# SEADLight.net
KiCad netlist of a schematic drawn in EAGLE
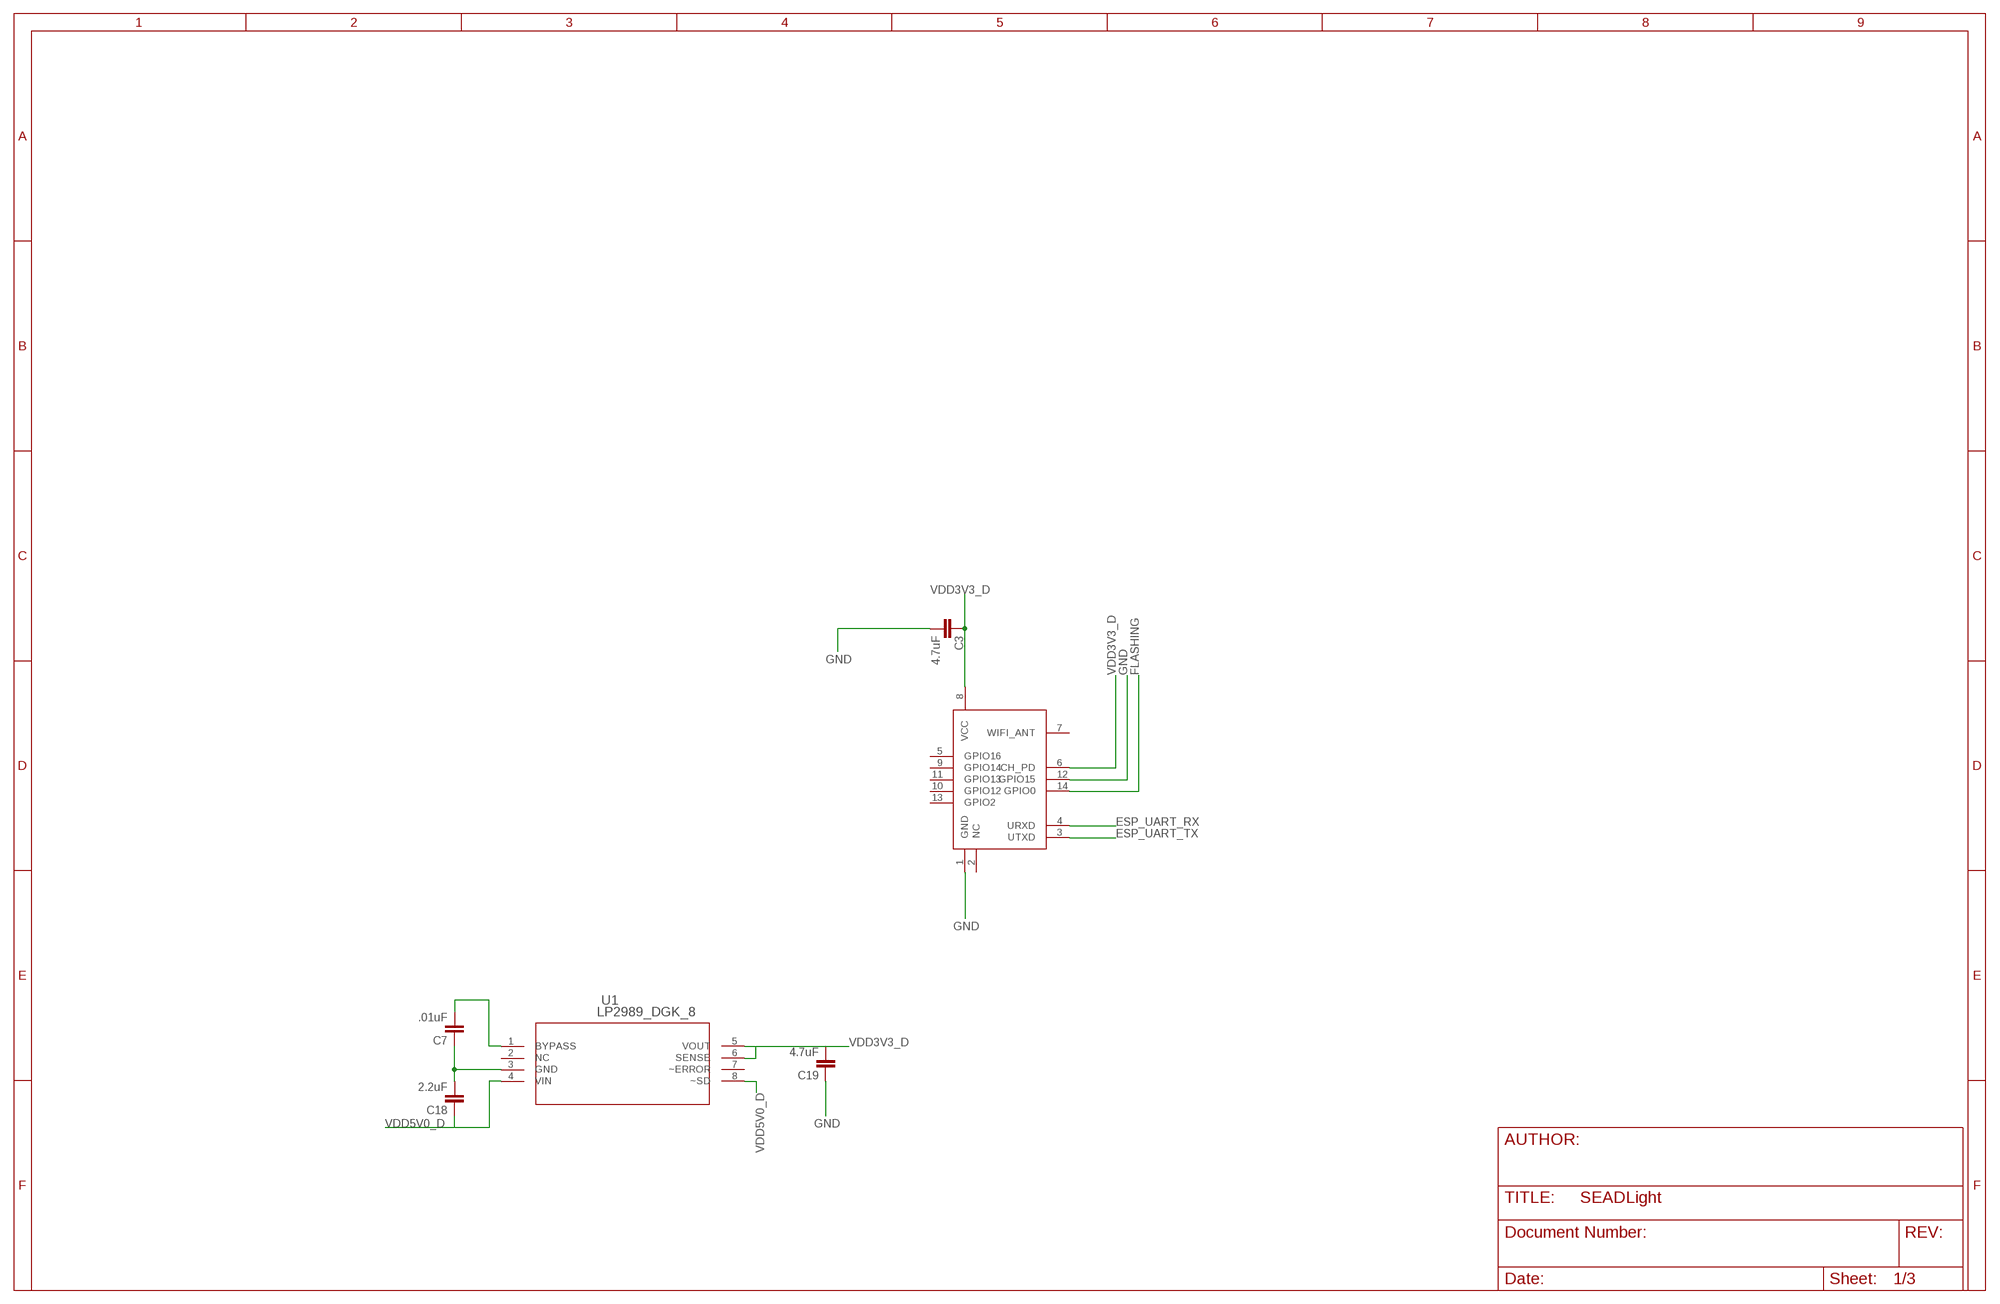
[diagram p0: schematic, sheet 1]
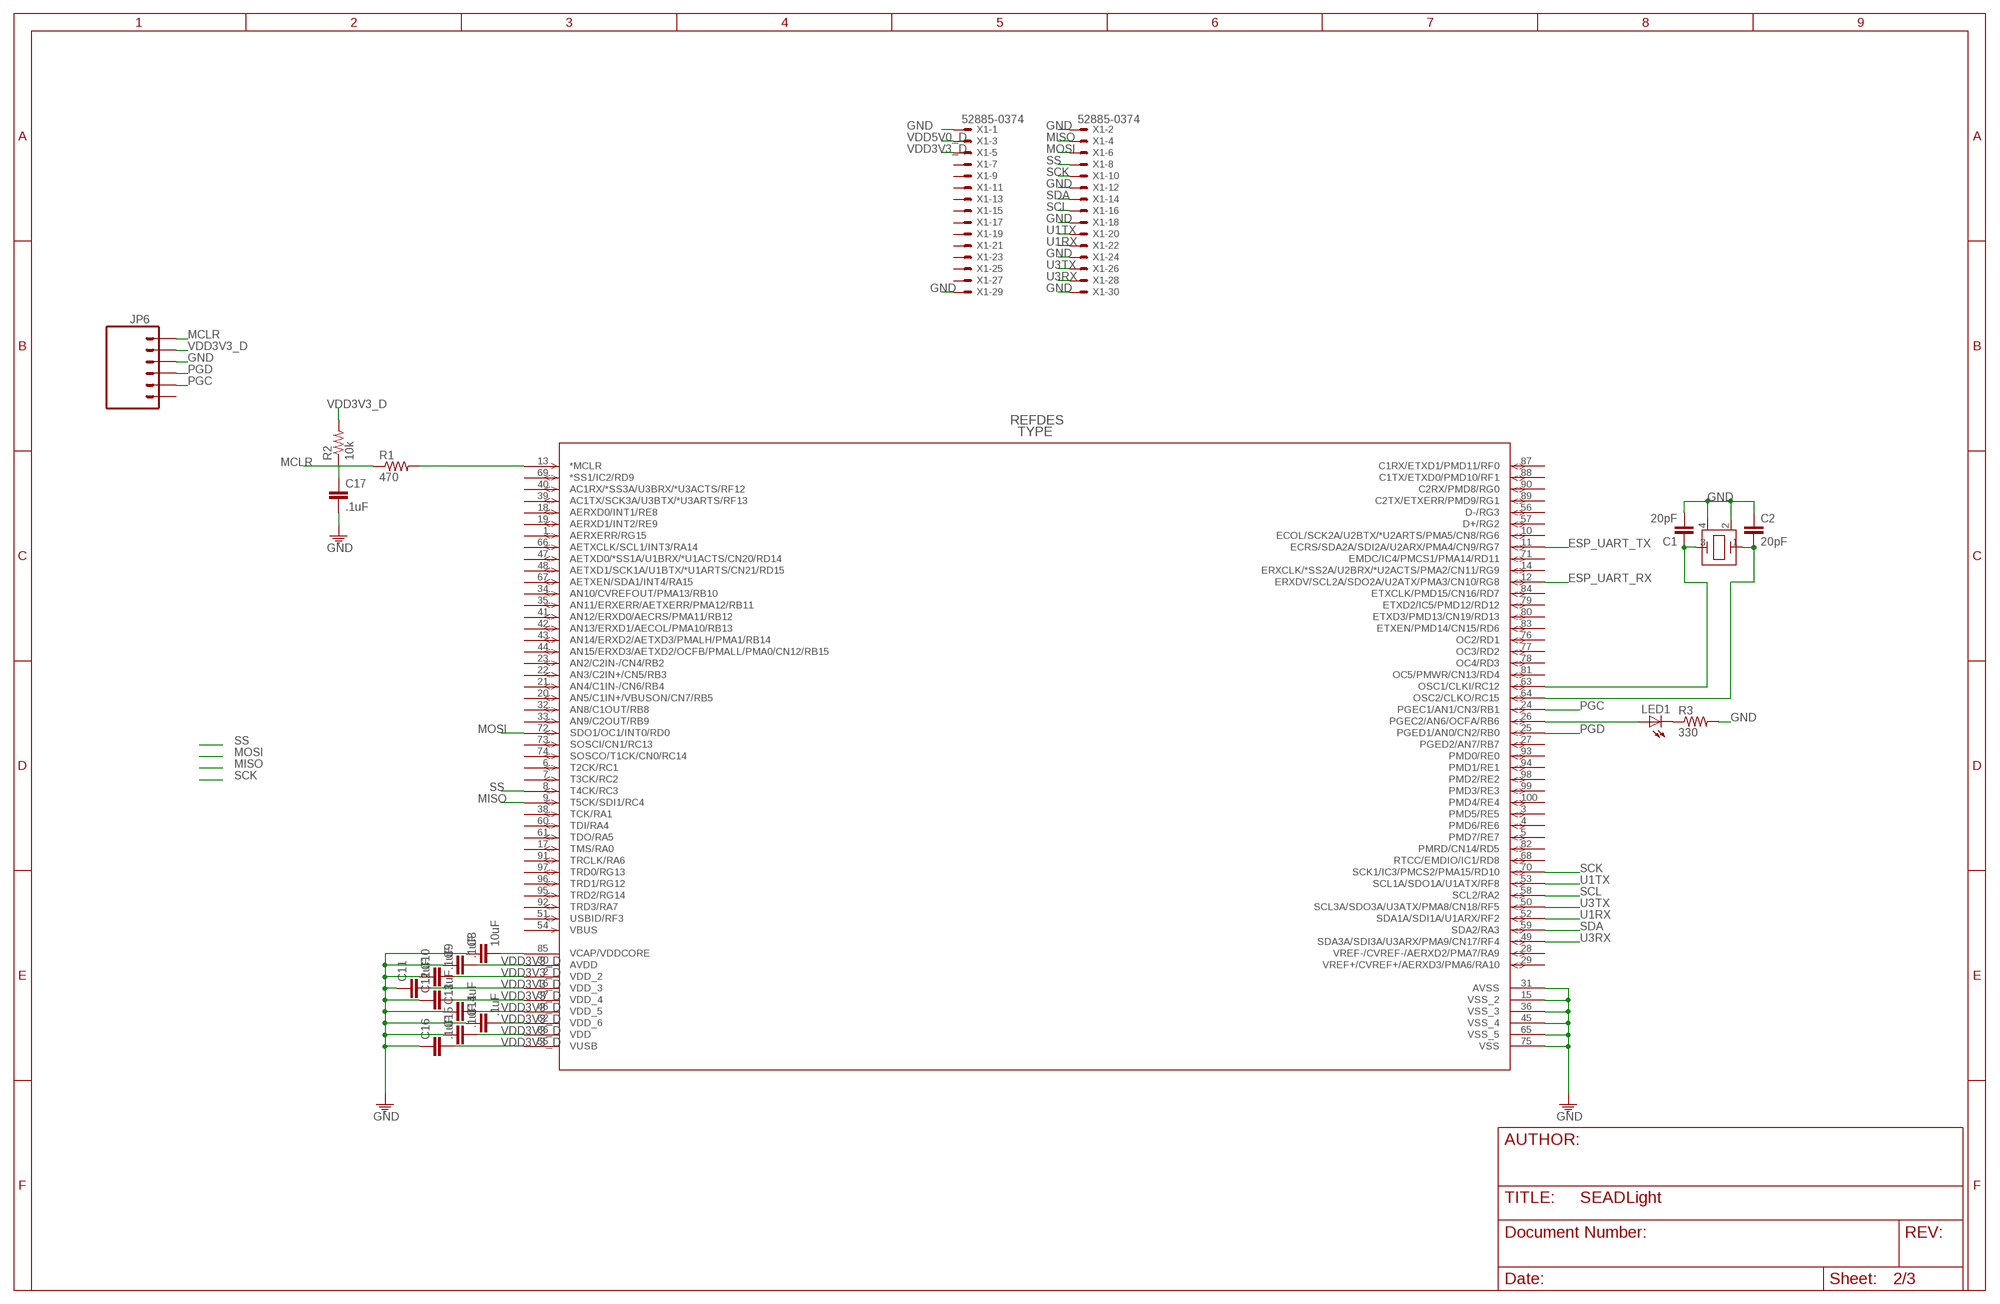
[diagram p1: schematic, sheet 2]
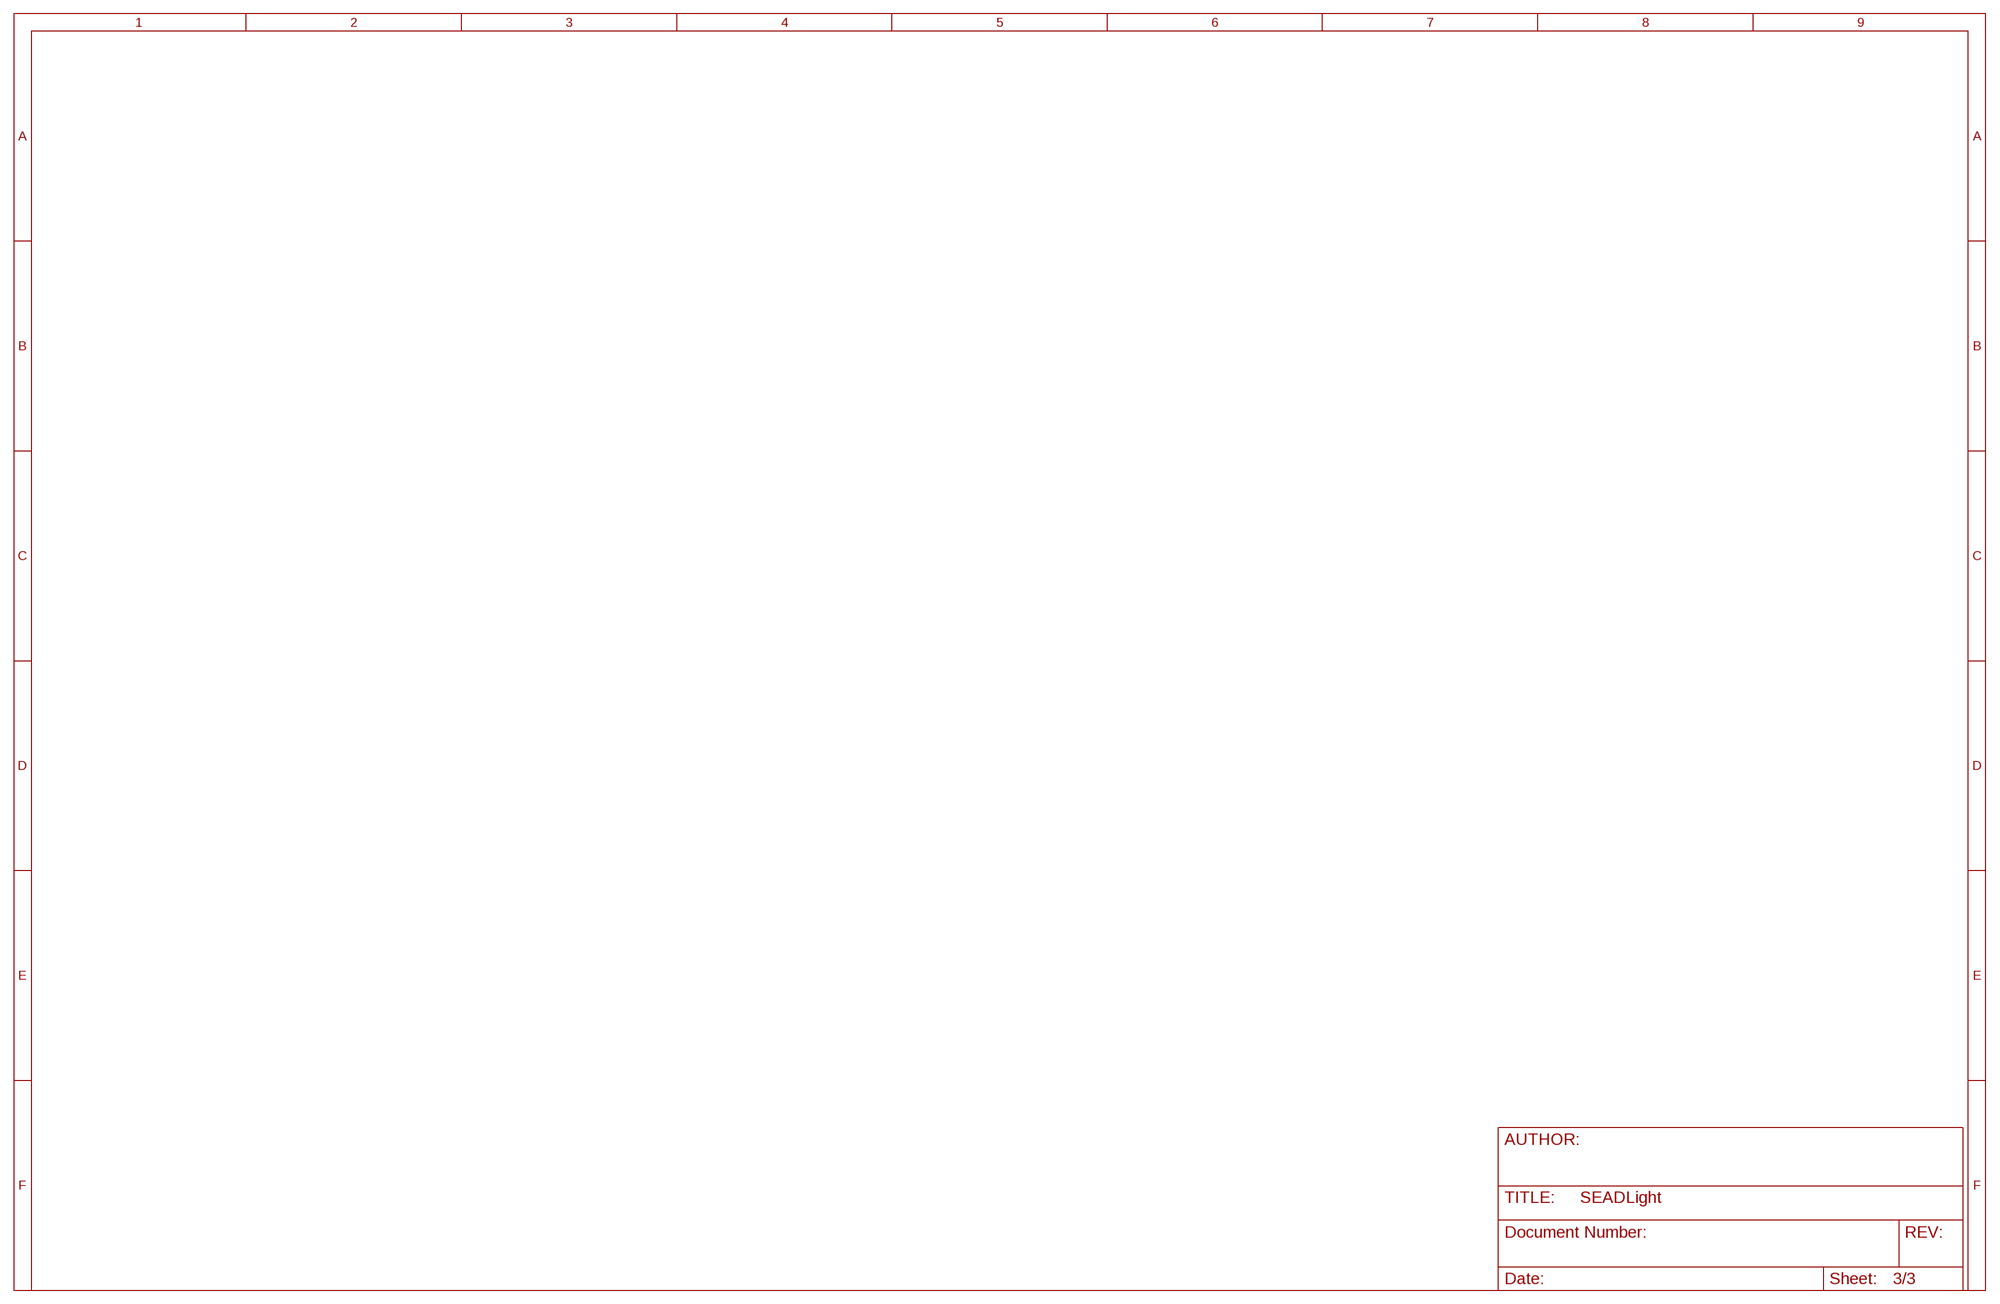
[diagram p2: schematic, sheet 3]

(export (version "E")
  (design (tool "Eeschema 10.0.6"))
  (components
    (comp (ref "C1")
      (value "20pF")
      (footprint "eagle-import:0805")
      (libsource (lib "eagle-import") (part "CAP0805"))
    )
    (comp (ref "C2")
      (value "20pF")
      (footprint "eagle-import:0805")
      (libsource (lib "eagle-import") (part "CAP0805"))
    )
    (comp (ref "C8")
      (value "10uF")
      (footprint "eagle-import:0805")
      (libsource (lib "eagle-import") (part "CAP0805"))
    )
    (comp (ref "C9")
      (value ".1uF")
      (footprint "eagle-import:0805")
      (libsource (lib "eagle-import") (part "CAP0805"))
    )
    (comp (ref "C10")
      (value ".1uF")
      (footprint "eagle-import:0805")
      (libsource (lib "eagle-import") (part "CAP0805"))
    )
    (comp (ref "C11")
      (value ".1uF")
      (footprint "eagle-import:0805")
      (libsource (lib "eagle-import") (part "CAP0805"))
    )
    (comp (ref "C12")
      (value ".1uF")
      (footprint "eagle-import:0805")
      (libsource (lib "eagle-import") (part "CAP0805"))
    )
    (comp (ref "C13")
      (value ".1uF")
      (footprint "eagle-import:0805")
      (libsource (lib "eagle-import") (part "CAP0805"))
    )
    (comp (ref "C14")
      (value ".1uF")
      (footprint "eagle-import:0805")
      (libsource (lib "eagle-import") (part "CAP0805"))
    )
    (comp (ref "C15")
      (value ".1uF")
      (footprint "eagle-import:0805")
      (libsource (lib "eagle-import") (part "CAP0805"))
    )
    (comp (ref "C16")
      (value ".1uF")
      (footprint "eagle-import:0805")
      (libsource (lib "eagle-import") (part "CAP0805"))
    )
    (comp (ref "C17")
      (value ".1uF")
      (footprint "eagle-import:0805")
      (libsource (lib "eagle-import") (part "CAP0805"))
    )
    (comp (ref "JP6")
      (value "M06SIP_LOCK")
      (footprint "eagle-import:1X06-SIP_LOCK")
      (libsource (lib "eagle-import") (part "M06SIP_LOCK"))
    )
    (comp (ref "LED1")
      (value "LED0805")
      (footprint "eagle-import:LED-0805")
      (libsource (lib "eagle-import") (part "LED0805"))
    )
    (comp (ref "R1")
      (value "470")
      (footprint "eagle-import:0805")
      (libsource (lib "eagle-import") (part "RESISTOR0805-RES"))
    )
    (comp (ref "R2")
      (value "10k")
      (footprint "eagle-import:0805")
      (libsource (lib "eagle-import") (part "RESISTOR0805-RES"))
    )
    (comp (ref "R3")
      (value "330")
      (footprint "eagle-import:0805")
      (libsource (lib "eagle-import") (part "RESISTOR0805-RES"))
    )
    (comp (ref "U$1")
      (value "PIC32MX795F512L-")
      (footprint "eagle-import:TQFP100_12X12MC")
      (libsource (lib "eagle-import") (part "PIC32MX795F512L-"))
    )
    (comp (ref "U$2")
      (value "ABM3B-8.000MHZ-10-1-U-T")
      (footprint "eagle-import:ABM3B")
      (libsource (lib "eagle-import") (part "ABM3B-8.000MHZ-10-1-U-T"))
    )
    (comp (ref "X1")
      (value "52885-0374")
      (footprint "eagle-import:52885-0374")
      (fields (field (name "MPN") "52760-0379"))
      (libsource (lib "eagle-import") (part "52885-0374"))
    )
    (comp (ref "C3")
      (value "4.7uF")
      (footprint "eagle-import:0805")
      (libsource (lib "eagle-import") (part "CAP0805"))
    )
    (comp (ref "C7")
      (value ".01uF")
      (footprint "eagle-import:0805")
      (libsource (lib "eagle-import") (part "CAP0805"))
    )
    (comp (ref "C18")
      (value "2.2uF")
      (footprint "eagle-import:0805")
      (libsource (lib "eagle-import") (part "CAP0805"))
    )
    (comp (ref "C19")
      (value "4.7uF")
      (footprint "eagle-import:0805")
      (libsource (lib "eagle-import") (part "CAP0805"))
    )
    (comp (ref "U$3")
      (value "EPS8266")
      (footprint "eagle-import:ESP8266-03")
      (libsource (lib "eagle-import") (part "EPS8266"))
    )
    (comp (ref "U1")
      (value "LP2989_DGK_8")
      (footprint "eagle-import:MUA08A")
      (fields (field (name "PARTNUMBER") "LP2989AIMM-25"))
      (libsource (lib "eagle-import") (part "LP2989_DGK_8"))
    )
  )
  (nets
    (net (code "1") (name "ESP_UART_RX") (class "Default")
      (node (ref "U$1") (pin "12") (pinfunction "ERXDV/SCL2A/SDO2A/U2ATX/PMA3/CN10/RG8_12") (pintype "passive"))
      (node (ref "U$3") (pin "4") (pinfunction "URXD_4") (pintype "bidirectional"))
    )
    (net (code "2") (name "ESP_UART_TX") (class "Default")
      (node (ref "U$1") (pin "11") (pinfunction "ECRS/SDA2A/SDI2A/U2ARX/PMA4/CN9/RG7_11") (pintype "passive"))
      (node (ref "U$3") (pin "3") (pinfunction "UTXD_3") (pintype "bidirectional"))
    )
    (net (code "3") (name "FLASHING") (class "Default")
      (node (ref "U$3") (pin "14") (pinfunction "GPIO0_14") (pintype "bidirectional"))
    )
    (net (code "4") (name "GND") (class "Default")
      (node (ref "C1") (pin "2") (pinfunction "2_2") (pintype "passive"))
      (node (ref "C10") (pin "1") (pinfunction "1_1") (pintype "passive"))
      (node (ref "C11") (pin "1") (pinfunction "1_1") (pintype "passive"))
      (node (ref "C12") (pin "1") (pinfunction "1_1") (pintype "passive"))
      (node (ref "C13") (pin "1") (pinfunction "1_1") (pintype "passive"))
      (node (ref "C14") (pin "1") (pinfunction "1_1") (pintype "passive"))
      (node (ref "C15") (pin "1") (pinfunction "1_1") (pintype "passive"))
      (node (ref "C16") (pin "1") (pinfunction "1_1") (pintype "passive"))
      (node (ref "C17") (pin "2") (pinfunction "2_2") (pintype "passive"))
      (node (ref "C18") (pin "2") (pinfunction "2_2") (pintype "passive"))
      (node (ref "C19") (pin "1") (pinfunction "1_1") (pintype "passive"))
      (node (ref "C2") (pin "1") (pinfunction "1_1") (pintype "passive"))
      (node (ref "C3") (pin "2") (pinfunction "2_2") (pintype "passive"))
      (node (ref "C7") (pin "1") (pinfunction "1_1") (pintype "passive"))
      (node (ref "C8") (pin "1") (pinfunction "1_1") (pintype "passive"))
      (node (ref "C9") (pin "1") (pinfunction "1_1") (pintype "passive"))
      (node (ref "JP6") (pin "3") (pinfunction "3_3") (pintype "passive"))
      (node (ref "R3") (pin "2") (pinfunction "2_2") (pintype "passive"))
      (node (ref "U$1") (pin "15") (pinfunction "VSS_2_15") (pintype "passive"))
      (node (ref "U$1") (pin "31") (pinfunction "AVSS_31") (pintype "passive"))
      (node (ref "U$1") (pin "36") (pinfunction "VSS_3_36") (pintype "passive"))
      (node (ref "U$1") (pin "45") (pinfunction "VSS_4_45") (pintype "passive"))
      (node (ref "U$1") (pin "65") (pinfunction "VSS_5_65") (pintype "passive"))
      (node (ref "U$1") (pin "75") (pinfunction "VSS_75") (pintype "passive"))
      (node (ref "U$2") (pin "2") (pinfunction "GND1_2") (pintype "bidirectional"))
      (node (ref "U$2") (pin "4") (pinfunction "GND2_4") (pintype "bidirectional"))
      (node (ref "U$3") (pin "1") (pinfunction "GND_1") (pintype "bidirectional"))
      (node (ref "U$3") (pin "12") (pinfunction "GPIO15_12") (pintype "bidirectional"))
      (node (ref "U1") (pin "3") (pinfunction "GND_3") (pintype "passive"))
      (node (ref "X1") (pin "1") (pinfunction "S_1") (pintype "passive"))
      (node (ref "X1") (pin "12") (pinfunction "S_12") (pintype "passive"))
      (node (ref "X1") (pin "18") (pinfunction "S_18") (pintype "passive"))
      (node (ref "X1") (pin "2") (pinfunction "S_2") (pintype "passive"))
      (node (ref "X1") (pin "24") (pinfunction "S_24") (pintype "passive"))
      (node (ref "X1") (pin "29") (pinfunction "S_29") (pintype "passive"))
      (node (ref "X1") (pin "30") (pinfunction "S_30") (pintype "passive"))
    )
    (net (code "5") (name "MCLR") (class "Default")
      (node (ref "C17") (pin "1") (pinfunction "1_1") (pintype "passive"))
      (node (ref "JP6") (pin "1") (pinfunction "1_1") (pintype "passive"))
      (node (ref "R1") (pin "1") (pinfunction "1_1") (pintype "passive"))
      (node (ref "R2") (pin "1") (pinfunction "1_1") (pintype "passive"))
    )
    (net (code "6") (name "MISO") (class "Default")
      (node (ref "U$1") (pin "9") (pinfunction "T5CK/SDI1/RC4_9") (pintype "passive"))
      (node (ref "X1") (pin "4") (pinfunction "S_4") (pintype "passive"))
    )
    (net (code "7") (name "MOSI") (class "Default")
      (node (ref "U$1") (pin "72") (pinfunction "SDO1/OC1/INT0/RD0_72") (pintype "passive"))
      (node (ref "X1") (pin "6") (pinfunction "S_6") (pintype "passive"))
    )
    (net (code "8") (name "Net-(LED1-A)") (class "Default")
      (node (ref "LED1") (pin "1") (pinfunction "A_1") (pintype "passive"))
      (node (ref "U$1") (pin "26") (pinfunction "PGEC2/AN6/OCFA/RB6_26") (pintype "passive"))
    )
    (net (code "9") (name "Net-(LED1-C)") (class "Default")
      (node (ref "LED1") (pin "2") (pinfunction "C_2") (pintype "passive"))
      (node (ref "R3") (pin "1") (pinfunction "1_1") (pintype "passive"))
    )
    (net (code "10") (name "Net-(U$1-*MCLR)") (class "Default")
      (node (ref "R1") (pin "2") (pinfunction "2_2") (pintype "passive"))
      (node (ref "U$1") (pin "13") (pinfunction "*MCLR_13") (pintype "passive"))
    )
    (net (code "11") (name "Net-(U$1-OSC1{slash}CLKI{slash}RC12)") (class "Default")
      (node (ref "C1") (pin "1") (pinfunction "1_1") (pintype "passive"))
      (node (ref "U$1") (pin "63") (pinfunction "OSC1/CLKI/RC12_63") (pintype "passive"))
      (node (ref "U$2") (pin "3") (pinfunction "OSC2_3") (pintype "bidirectional"))
    )
    (net (code "12") (name "Net-(U$1-OSC2{slash}CLKO{slash}RC15)") (class "Default")
      (node (ref "C2") (pin "2") (pinfunction "2_2") (pintype "passive"))
      (node (ref "U$1") (pin "64") (pinfunction "OSC2/CLKO/RC15_64") (pintype "passive"))
      (node (ref "U$2") (pin "1") (pinfunction "OSC1_1") (pintype "bidirectional"))
    )
    (net (code "13") (name "Net-(U$1-VCAP{slash}VDDCORE)") (class "Default")
      (node (ref "C8") (pin "2") (pinfunction "2_2") (pintype "passive"))
      (node (ref "U$1") (pin "85") (pinfunction "VCAP/VDDCORE_85") (pintype "passive"))
    )
    (net (code "14") (name "Net-(U1-BYPASS)") (class "Default")
      (node (ref "C7") (pin "2") (pinfunction "2_2") (pintype "passive"))
      (node (ref "U1") (pin "1") (pinfunction "BYPASS_1") (pintype "passive"))
    )
    (net (code "15") (name "PGC") (class "Default")
      (node (ref "JP6") (pin "5") (pinfunction "5_5") (pintype "passive"))
      (node (ref "U$1") (pin "24") (pinfunction "PGEC1/AN1/CN3/RB1_24") (pintype "passive"))
    )
    (net (code "16") (name "PGD") (class "Default")
      (node (ref "JP6") (pin "4") (pinfunction "4_4") (pintype "passive"))
      (node (ref "U$1") (pin "25") (pinfunction "PGED1/AN0/CN2/RB0_25") (pintype "passive"))
    )
    (net (code "17") (name "SCK") (class "Default")
      (node (ref "U$1") (pin "70") (pinfunction "SCK1/IC3/PMCS2/PMA15/RD10_70") (pintype "passive"))
      (node (ref "X1") (pin "10") (pinfunction "S_10") (pintype "passive"))
    )
    (net (code "18") (name "SCL") (class "Default")
      (node (ref "U$1") (pin "58") (pinfunction "SCL2/RA2_58") (pintype "passive"))
      (node (ref "X1") (pin "16") (pinfunction "S_16") (pintype "passive"))
    )
    (net (code "19") (name "SDA") (class "Default")
      (node (ref "U$1") (pin "59") (pinfunction "SDA2/RA3_59") (pintype "passive"))
      (node (ref "X1") (pin "14") (pinfunction "S_14") (pintype "passive"))
    )
    (net (code "20") (name "SS") (class "Default")
      (node (ref "U$1") (pin "8") (pinfunction "T4CK/RC3_8") (pintype "passive"))
      (node (ref "X1") (pin "8") (pinfunction "S_8") (pintype "passive"))
    )
    (net (code "21") (name "U1RX") (class "Default")
      (node (ref "U$1") (pin "52") (pinfunction "SDA1A/SDI1A/U1ARX/RF2_52") (pintype "passive"))
      (node (ref "X1") (pin "22") (pinfunction "S_22") (pintype "passive"))
    )
    (net (code "22") (name "U1TX") (class "Default")
      (node (ref "U$1") (pin "53") (pinfunction "SCL1A/SDO1A/U1ATX/RF8_53") (pintype "passive"))
      (node (ref "X1") (pin "20") (pinfunction "S_20") (pintype "passive"))
    )
    (net (code "23") (name "U3RX") (class "Default")
      (node (ref "U$1") (pin "49") (pinfunction "SDA3A/SDI3A/U3ARX/PMA9/CN17/RF4_49") (pintype "passive"))
      (node (ref "X1") (pin "28") (pinfunction "S_28") (pintype "passive"))
    )
    (net (code "24") (name "U3TX") (class "Default")
      (node (ref "U$1") (pin "50") (pinfunction "SCL3A/SDO3A/U3ATX/PMA8/CN18/RF5_50") (pintype "passive"))
      (node (ref "X1") (pin "26") (pinfunction "S_26") (pintype "passive"))
    )
    (net (code "25") (name "VDD3V3_D") (class "Default")
      (node (ref "C10") (pin "2") (pinfunction "2_2") (pintype "passive"))
      (node (ref "C11") (pin "2") (pinfunction "2_2") (pintype "passive"))
      (node (ref "C12") (pin "2") (pinfunction "2_2") (pintype "passive"))
      (node (ref "C13") (pin "2") (pinfunction "2_2") (pintype "passive"))
      (node (ref "C14") (pin "2") (pinfunction "2_2") (pintype "passive"))
      (node (ref "C15") (pin "2") (pinfunction "2_2") (pintype "passive"))
      (node (ref "C16") (pin "2") (pinfunction "2_2") (pintype "passive"))
      (node (ref "C19") (pin "2") (pinfunction "2_2") (pintype "passive"))
      (node (ref "C3") (pin "1") (pinfunction "1_1") (pintype "passive"))
      (node (ref "C9") (pin "2") (pinfunction "2_2") (pintype "passive"))
      (node (ref "JP6") (pin "2") (pinfunction "2_2") (pintype "passive"))
      (node (ref "R2") (pin "2") (pinfunction "2_2") (pintype "passive"))
      (node (ref "U$1") (pin "16") (pinfunction "VDD_3_16") (pintype "passive"))
      (node (ref "U$1") (pin "2") (pinfunction "VDD_2_2") (pintype "passive"))
      (node (ref "U$1") (pin "30") (pinfunction "AVDD_30") (pintype "passive"))
      (node (ref "U$1") (pin "37") (pinfunction "VDD_4_37") (pintype "passive"))
      (node (ref "U$1") (pin "46") (pinfunction "VDD_5_46") (pintype "passive"))
      (node (ref "U$1") (pin "55") (pinfunction "VUSB_55") (pintype "passive"))
      (node (ref "U$1") (pin "62") (pinfunction "VDD_6_62") (pintype "passive"))
      (node (ref "U$1") (pin "86") (pinfunction "VDD_86") (pintype "passive"))
      (node (ref "U$3") (pin "6") (pinfunction "CH_PD_6") (pintype "bidirectional"))
      (node (ref "U$3") (pin "8") (pinfunction "VCC_8") (pintype "bidirectional"))
      (node (ref "U1") (pin "5") (pinfunction "VOUT_5") (pintype "output"))
      (node (ref "U1") (pin "6") (pinfunction "SENSE_6") (pintype "passive"))
      (node (ref "X1") (pin "5") (pinfunction "S_5") (pintype "passive"))
    )
    (net (code "26") (name "VDD5V0_D") (class "Default")
      (node (ref "C18") (pin "1") (pinfunction "1_1") (pintype "passive"))
      (node (ref "U1") (pin "4") (pinfunction "VIN_4") (pintype "input"))
      (node (ref "U1") (pin "8") (pinfunction "~{SD}_8") (pintype "passive"))
      (node (ref "X1") (pin "3") (pinfunction "S_3") (pintype "passive"))
    )
    (net (code "27") (name "unconnected-(JP6-Pad6)") (class "Default")
      (node (ref "JP6") (pin "6") (pinfunction "6_6") (pintype "passive"))
    )
    (net (code "28") (name "unconnected-(U$1-*SS1{slash}IC2{slash}RD9-Pad69)") (class "Default")
      (node (ref "U$1") (pin "69") (pinfunction "*SS1/IC2/RD9_69") (pintype "passive"))
    )
    (net (code "29") (name "unconnected-(U$1-AC1RX{slash}*SS3A{slash}U3BRX{slash}*U3ACTS{slash}RF12-Pad40)") (class "Default")
      (node (ref "U$1") (pin "40") (pinfunction "AC1RX/*SS3A/U3BRX/*U3ACTS/RF12_40") (pintype "passive"))
    )
    (net (code "30") (name "unconnected-(U$1-AC1TX{slash}SCK3A{slash}U3BTX{slash}*U3ARTS{slash}RF13-Pad39)") (class "Default")
      (node (ref "U$1") (pin "39") (pinfunction "AC1TX/SCK3A/U3BTX/*U3ARTS/RF13_39") (pintype "passive"))
    )
    (net (code "31") (name "unconnected-(U$1-AERXD0{slash}INT1{slash}RE8-Pad18)") (class "Default")
      (node (ref "U$1") (pin "18") (pinfunction "AERXD0/INT1/RE8_18") (pintype "passive"))
    )
    (net (code "32") (name "unconnected-(U$1-AERXD1{slash}INT2{slash}RE9-Pad19)") (class "Default")
      (node (ref "U$1") (pin "19") (pinfunction "AERXD1/INT2/RE9_19") (pintype "passive"))
    )
    (net (code "33") (name "unconnected-(U$1-AERXERR{slash}RG15-Pad1)") (class "Default")
      (node (ref "U$1") (pin "1") (pinfunction "AERXERR/RG15_1") (pintype "passive"))
    )
    (net (code "34") (name "unconnected-(U$1-AETXCLK{slash}SCL1{slash}INT3{slash}RA14-Pad66)") (class "Default")
      (node (ref "U$1") (pin "66") (pinfunction "AETXCLK/SCL1/INT3/RA14_66") (pintype "passive"))
    )
    (net (code "35") (name "unconnected-(U$1-AETXD0{slash}*SS1A{slash}U1BRX{slash}*U1ACTS{slash}CN20{slash}RD14-Pad47)") (class "Default")
      (node (ref "U$1") (pin "47") (pinfunction "AETXD0/*SS1A/U1BRX/*U1ACTS/CN20/RD14_47") (pintype "passive"))
    )
    (net (code "36") (name "unconnected-(U$1-AETXD1{slash}SCK1A{slash}U1BTX{slash}*U1ARTS{slash}CN21{slash}RD15-Pad48)") (class "Default")
      (node (ref "U$1") (pin "48") (pinfunction "AETXD1/SCK1A/U1BTX/*U1ARTS/CN21/RD15_48") (pintype "passive"))
    )
    (net (code "37") (name "unconnected-(U$1-AETXEN{slash}SDA1{slash}INT4{slash}RA15-Pad67)") (class "Default")
      (node (ref "U$1") (pin "67") (pinfunction "AETXEN/SDA1/INT4/RA15_67") (pintype "passive"))
    )
    (net (code "38") (name "unconnected-(U$1-AN2{slash}C2IN-{slash}CN4{slash}RB2-Pad23)") (class "Default")
      (node (ref "U$1") (pin "23") (pinfunction "AN2/C2IN-/CN4/RB2_23") (pintype "passive"))
    )
    (net (code "39") (name "unconnected-(U$1-AN3{slash}C2IN+{slash}CN5{slash}RB3-Pad22)") (class "Default")
      (node (ref "U$1") (pin "22") (pinfunction "AN3/C2IN+/CN5/RB3_22") (pintype "passive"))
    )
    (net (code "40") (name "unconnected-(U$1-AN4{slash}C1IN-{slash}CN6{slash}RB4-Pad21)") (class "Default")
      (node (ref "U$1") (pin "21") (pinfunction "AN4/C1IN-/CN6/RB4_21") (pintype "passive"))
    )
    (net (code "41") (name "unconnected-(U$1-AN5{slash}C1IN+{slash}VBUSON{slash}CN7{slash}RB5-Pad20)") (class "Default")
      (node (ref "U$1") (pin "20") (pinfunction "AN5/C1IN+/VBUSON/CN7/RB5_20") (pintype "passive"))
    )
    (net (code "42") (name "unconnected-(U$1-AN8{slash}C1OUT{slash}RB8-Pad32)") (class "Default")
      (node (ref "U$1") (pin "32") (pinfunction "AN8/C1OUT/RB8_32") (pintype "passive"))
    )
    (net (code "43") (name "unconnected-(U$1-AN9{slash}C2OUT{slash}RB9-Pad33)") (class "Default")
      (node (ref "U$1") (pin "33") (pinfunction "AN9/C2OUT/RB9_33") (pintype "passive"))
    )
    (net (code "44") (name "unconnected-(U$1-AN10{slash}CVREFOUT{slash}PMA13{slash}RB10-Pad34)") (class "Default")
      (node (ref "U$1") (pin "34") (pinfunction "AN10/CVREFOUT/PMA13/RB10_34") (pintype "passive"))
    )
    (net (code "45") (name "unconnected-(U$1-AN11{slash}ERXERR{slash}AETXERR{slash}PMA12{slash}RB11-Pad35)") (class "Default")
      (node (ref "U$1") (pin "35") (pinfunction "AN11/ERXERR/AETXERR/PMA12/RB11_35") (pintype "passive"))
    )
    (net (code "46") (name "unconnected-(U$1-AN12{slash}ERXD0{slash}AECRS{slash}PMA11{slash}RB12-Pad41)") (class "Default")
      (node (ref "U$1") (pin "41") (pinfunction "AN12/ERXD0/AECRS/PMA11/RB12_41") (pintype "passive"))
    )
    (net (code "47") (name "unconnected-(U$1-AN13{slash}ERXD1{slash}AECOL{slash}PMA10{slash}RB13-Pad42)") (class "Default")
      (node (ref "U$1") (pin "42") (pinfunction "AN13/ERXD1/AECOL/PMA10/RB13_42") (pintype "passive"))
    )
    (net (code "48") (name "unconnected-(U$1-AN14{slash}ERXD2{slash}AETXD3{slash}PMALH{slash}PMA1{slash}RB14-Pad43)") (class "Default")
      (node (ref "U$1") (pin "43") (pinfunction "AN14/ERXD2/AETXD3/PMALH/PMA1/RB14_43") (pintype "passive"))
    )
    (net (code "49") (name "unconnected-(U$1-AN15{slash}ERXD3{slash}AETXD2{slash}OCFB{slash}PMALL{slash}PMA0{slash}CN12{slash}RB15-Pad44)") (class "Default")
      (node (ref "U$1") (pin "44") (pinfunction "AN15/ERXD3/AETXD2/OCFB/PMALL/PMA0/CN12/RB15_44") (pintype "passive"))
    )
    (net (code "50") (name "unconnected-(U$1-C1RX{slash}ETXD1{slash}PMD11{slash}RF0-Pad87)") (class "Default")
      (node (ref "U$1") (pin "87") (pinfunction "C1RX/ETXD1/PMD11/RF0_87") (pintype "passive"))
    )
    (net (code "51") (name "unconnected-(U$1-C1TX{slash}ETXD0{slash}PMD10{slash}RF1-Pad88)") (class "Default")
      (node (ref "U$1") (pin "88") (pinfunction "C1TX/ETXD0/PMD10/RF1_88") (pintype "passive"))
    )
    (net (code "52") (name "unconnected-(U$1-C2RX{slash}PMD8{slash}RG0-Pad90)") (class "Default")
      (node (ref "U$1") (pin "90") (pinfunction "C2RX/PMD8/RG0_90") (pintype "passive"))
    )
    (net (code "53") (name "unconnected-(U$1-C2TX{slash}ETXERR{slash}PMD9{slash}RG1-Pad89)") (class "Default")
      (node (ref "U$1") (pin "89") (pinfunction "C2TX/ETXERR/PMD9/RG1_89") (pintype "passive"))
    )
    (net (code "54") (name "unconnected-(U$1-D+{slash}RG2-Pad57)") (class "Default")
      (node (ref "U$1") (pin "57") (pinfunction "D+/RG2_57") (pintype "passive"))
    )
    (net (code "55") (name "unconnected-(U$1-D-{slash}RG3-Pad56)") (class "Default")
      (node (ref "U$1") (pin "56") (pinfunction "D-/RG3_56") (pintype "passive"))
    )
    (net (code "56") (name "unconnected-(U$1-ECOL{slash}SCK2A{slash}U2BTX{slash}*U2ARTS{slash}PMA5{slash}CN8{slash}RG6-Pad10)") (class "Default")
      (node (ref "U$1") (pin "10") (pinfunction "ECOL/SCK2A/U2BTX/*U2ARTS/PMA5/CN8/RG6_10") (pintype "passive"))
    )
    (net (code "57") (name "unconnected-(U$1-EMDC{slash}IC4{slash}PMCS1{slash}PMA14{slash}RD11-Pad71)") (class "Default")
      (node (ref "U$1") (pin "71") (pinfunction "EMDC/IC4/PMCS1/PMA14/RD11_71") (pintype "passive"))
    )
    (net (code "58") (name "unconnected-(U$1-ERXCLK{slash}*SS2A{slash}U2BRX{slash}*U2ACTS{slash}PMA2{slash}CN11{slash}RG9-Pad14)") (class "Default")
      (node (ref "U$1") (pin "14") (pinfunction "ERXCLK/*SS2A/U2BRX/*U2ACTS/PMA2/CN11/RG9_14") (pintype "passive"))
    )
    (net (code "59") (name "unconnected-(U$1-ETXCLK{slash}PMD15{slash}CN16{slash}RD7-Pad84)") (class "Default")
      (node (ref "U$1") (pin "84") (pinfunction "ETXCLK/PMD15/CN16/RD7_84") (pintype "passive"))
    )
    (net (code "60") (name "unconnected-(U$1-ETXD2{slash}IC5{slash}PMD12{slash}RD12-Pad79)") (class "Default")
      (node (ref "U$1") (pin "79") (pinfunction "ETXD2/IC5/PMD12/RD12_79") (pintype "passive"))
    )
    (net (code "61") (name "unconnected-(U$1-ETXD3{slash}PMD13{slash}CN19{slash}RD13-Pad80)") (class "Default")
      (node (ref "U$1") (pin "80") (pinfunction "ETXD3/PMD13/CN19/RD13_80") (pintype "passive"))
    )
    (net (code "62") (name "unconnected-(U$1-ETXEN{slash}PMD14{slash}CN15{slash}RD6-Pad83)") (class "Default")
      (node (ref "U$1") (pin "83") (pinfunction "ETXEN/PMD14/CN15/RD6_83") (pintype "passive"))
    )
    (net (code "63") (name "unconnected-(U$1-OC2{slash}RD1-Pad76)") (class "Default")
      (node (ref "U$1") (pin "76") (pinfunction "OC2/RD1_76") (pintype "passive"))
    )
    (net (code "64") (name "unconnected-(U$1-OC3{slash}RD2-Pad77)") (class "Default")
      (node (ref "U$1") (pin "77") (pinfunction "OC3/RD2_77") (pintype "passive"))
    )
    (net (code "65") (name "unconnected-(U$1-OC4{slash}RD3-Pad78)") (class "Default")
      (node (ref "U$1") (pin "78") (pinfunction "OC4/RD3_78") (pintype "passive"))
    )
    (net (code "66") (name "unconnected-(U$1-OC5{slash}PMWR{slash}CN13{slash}RD4-Pad81)") (class "Default")
      (node (ref "U$1") (pin "81") (pinfunction "OC5/PMWR/CN13/RD4_81") (pintype "passive"))
    )
    (net (code "67") (name "unconnected-(U$1-PGED2{slash}AN7{slash}RB7-Pad27)") (class "Default")
      (node (ref "U$1") (pin "27") (pinfunction "PGED2/AN7/RB7_27") (pintype "passive"))
    )
    (net (code "68") (name "unconnected-(U$1-PMD0{slash}RE0-Pad93)") (class "Default")
      (node (ref "U$1") (pin "93") (pinfunction "PMD0/RE0_93") (pintype "passive"))
    )
    (net (code "69") (name "unconnected-(U$1-PMD1{slash}RE1-Pad94)") (class "Default")
      (node (ref "U$1") (pin "94") (pinfunction "PMD1/RE1_94") (pintype "passive"))
    )
    (net (code "70") (name "unconnected-(U$1-PMD2{slash}RE2-Pad98)") (class "Default")
      (node (ref "U$1") (pin "98") (pinfunction "PMD2/RE2_98") (pintype "passive"))
    )
    (net (code "71") (name "unconnected-(U$1-PMD3{slash}RE3-Pad99)") (class "Default")
      (node (ref "U$1") (pin "99") (pinfunction "PMD3/RE3_99") (pintype "passive"))
    )
    (net (code "72") (name "unconnected-(U$1-PMD4{slash}RE4-Pad100)") (class "Default")
      (node (ref "U$1") (pin "100") (pinfunction "PMD4/RE4_100") (pintype "passive"))
    )
    (net (code "73") (name "unconnected-(U$1-PMD5{slash}RE5-Pad3)") (class "Default")
      (node (ref "U$1") (pin "3") (pinfunction "PMD5/RE5_3") (pintype "passive"))
    )
    (net (code "74") (name "unconnected-(U$1-PMD6{slash}RE6-Pad4)") (class "Default")
      (node (ref "U$1") (pin "4") (pinfunction "PMD6/RE6_4") (pintype "passive"))
    )
    (net (code "75") (name "unconnected-(U$1-PMD7{slash}RE7-Pad5)") (class "Default")
      (node (ref "U$1") (pin "5") (pinfunction "PMD7/RE7_5") (pintype "passive"))
    )
    (net (code "76") (name "unconnected-(U$1-PMRD{slash}CN14{slash}RD5-Pad82)") (class "Default")
      (node (ref "U$1") (pin "82") (pinfunction "PMRD/CN14/RD5_82") (pintype "passive"))
    )
    (net (code "77") (name "unconnected-(U$1-RTCC{slash}EMDIO{slash}IC1{slash}RD8-Pad68)") (class "Default")
      (node (ref "U$1") (pin "68") (pinfunction "RTCC/EMDIO/IC1/RD8_68") (pintype "passive"))
    )
    (net (code "78") (name "unconnected-(U$1-SOSCI{slash}CN1{slash}RC13-Pad73)") (class "Default")
      (node (ref "U$1") (pin "73") (pinfunction "SOSCI/CN1/RC13_73") (pintype "passive"))
    )
    (net (code "79") (name "unconnected-(U$1-SOSCO{slash}T1CK{slash}CN0{slash}RC14-Pad74)") (class "Default")
      (node (ref "U$1") (pin "74") (pinfunction "SOSCO/T1CK/CN0/RC14_74") (pintype "passive"))
    )
    (net (code "80") (name "unconnected-(U$1-T2CK{slash}RC1-Pad6)") (class "Default")
      (node (ref "U$1") (pin "6") (pinfunction "T2CK/RC1_6") (pintype "passive"))
    )
    (net (code "81") (name "unconnected-(U$1-T3CK{slash}RC2-Pad7)") (class "Default")
      (node (ref "U$1") (pin "7") (pinfunction "T3CK/RC2_7") (pintype "passive"))
    )
    (net (code "82") (name "unconnected-(U$1-TCK{slash}RA1-Pad38)") (class "Default")
      (node (ref "U$1") (pin "38") (pinfunction "TCK/RA1_38") (pintype "passive"))
    )
    (net (code "83") (name "unconnected-(U$1-TDI{slash}RA4-Pad60)") (class "Default")
      (node (ref "U$1") (pin "60") (pinfunction "TDI/RA4_60") (pintype "passive"))
    )
    (net (code "84") (name "unconnected-(U$1-TDO{slash}RA5-Pad61)") (class "Default")
      (node (ref "U$1") (pin "61") (pinfunction "TDO/RA5_61") (pintype "passive"))
    )
    (net (code "85") (name "unconnected-(U$1-TMS{slash}RA0-Pad17)") (class "Default")
      (node (ref "U$1") (pin "17") (pinfunction "TMS/RA0_17") (pintype "passive"))
    )
    (net (code "86") (name "unconnected-(U$1-TRCLK{slash}RA6-Pad91)") (class "Default")
      (node (ref "U$1") (pin "91") (pinfunction "TRCLK/RA6_91") (pintype "passive"))
    )
    (net (code "87") (name "unconnected-(U$1-TRD0{slash}RG13-Pad97)") (class "Default")
      (node (ref "U$1") (pin "97") (pinfunction "TRD0/RG13_97") (pintype "passive"))
    )
    (net (code "88") (name "unconnected-(U$1-TRD1{slash}RG12-Pad96)") (class "Default")
      (node (ref "U$1") (pin "96") (pinfunction "TRD1/RG12_96") (pintype "passive"))
    )
    (net (code "89") (name "unconnected-(U$1-TRD2{slash}RG14-Pad95)") (class "Default")
      (node (ref "U$1") (pin "95") (pinfunction "TRD2/RG14_95") (pintype "passive"))
    )
    (net (code "90") (name "unconnected-(U$1-TRD3{slash}RA7-Pad92)") (class "Default")
      (node (ref "U$1") (pin "92") (pinfunction "TRD3/RA7_92") (pintype "passive"))
    )
    (net (code "91") (name "unconnected-(U$1-USBID{slash}RF3-Pad51)") (class "Default")
      (node (ref "U$1") (pin "51") (pinfunction "USBID/RF3_51") (pintype "passive"))
    )
    (net (code "92") (name "unconnected-(U$1-VBUS-Pad54)") (class "Default")
      (node (ref "U$1") (pin "54") (pinfunction "VBUS_54") (pintype "passive"))
    )
    (net (code "93") (name "unconnected-(U$1-VREF+{slash}CVREF+{slash}AERXD3{slash}PMA6{slash}RA10-Pad29)") (class "Default")
      (node (ref "U$1") (pin "29") (pinfunction "VREF+/CVREF+/AERXD3/PMA6/RA10_29") (pintype "passive"))
    )
    (net (code "94") (name "unconnected-(U$1-VREF-{slash}CVREF-{slash}AERXD2{slash}PMA7{slash}RA9-Pad28)") (class "Default")
      (node (ref "U$1") (pin "28") (pinfunction "VREF-/CVREF-/AERXD2/PMA7/RA9_28") (pintype "passive"))
    )
    (net (code "95") (name "unconnected-(U$3-GPIO2-Pad13)") (class "Default")
      (node (ref "U$3") (pin "13") (pinfunction "GPIO2_13") (pintype "bidirectional"))
    )
    (net (code "96") (name "unconnected-(U$3-GPIO12-Pad10)") (class "Default")
      (node (ref "U$3") (pin "10") (pinfunction "GPIO12_10") (pintype "bidirectional"))
    )
    (net (code "97") (name "unconnected-(U$3-GPIO13-Pad11)") (class "Default")
      (node (ref "U$3") (pin "11") (pinfunction "GPIO13_11") (pintype "bidirectional"))
    )
    (net (code "98") (name "unconnected-(U$3-GPIO14-Pad9)") (class "Default")
      (node (ref "U$3") (pin "9") (pinfunction "GPIO14_9") (pintype "bidirectional"))
    )
    (net (code "99") (name "unconnected-(U$3-GPIO16-Pad5)") (class "Default")
      (node (ref "U$3") (pin "5") (pinfunction "GPIO16_5") (pintype "bidirectional"))
    )
    (net (code "100") (name "unconnected-(U$3-NC-Pad2)") (class "Default")
      (node (ref "U$3") (pin "2") (pinfunction "NC_2") (pintype "bidirectional"))
    )
    (net (code "101") (name "unconnected-(U$3-WIFI_ANT-Pad7)") (class "Default")
      (node (ref "U$3") (pin "7") (pinfunction "WIFI_ANT_7") (pintype "bidirectional"))
    )
    (net (code "102") (name "unconnected-(U1-NC-Pad2)") (class "Default")
      (node (ref "U1") (pin "2") (pinfunction "NC_2") (pintype "passive"))
    )
    (net (code "103") (name "unconnected-(U1-~{ERROR}-Pad7)") (class "Default")
      (node (ref "U1") (pin "7") (pinfunction "~{ERROR}_7") (pintype "passive"))
    )
    (net (code "104") (name "unconnected-(X1AB-S-Pad7)") (class "Default")
      (node (ref "X1") (pin "7") (pinfunction "S_7") (pintype "passive"))
    )
    (net (code "105") (name "unconnected-(X1AD-S-Pad9)") (class "Default")
      (node (ref "X1") (pin "9") (pinfunction "S_9") (pintype "passive"))
    )
    (net (code "106") (name "unconnected-(X1C-S-Pad11)") (class "Default")
      (node (ref "X1") (pin "11") (pinfunction "S_11") (pintype "passive"))
    )
    (net (code "107") (name "unconnected-(X1E-S-Pad13)") (class "Default")
      (node (ref "X1") (pin "13") (pinfunction "S_13") (pintype "passive"))
    )
    (net (code "108") (name "unconnected-(X1G-S-Pad15)") (class "Default")
      (node (ref "X1") (pin "15") (pinfunction "S_15") (pintype "passive"))
    )
    (net (code "109") (name "unconnected-(X1I-S-Pad17)") (class "Default")
      (node (ref "X1") (pin "17") (pinfunction "S_17") (pintype "passive"))
    )
    (net (code "110") (name "unconnected-(X1K-S-Pad19)") (class "Default")
      (node (ref "X1") (pin "19") (pinfunction "S_19") (pintype "passive"))
    )
    (net (code "111") (name "unconnected-(X1N-S-Pad21)") (class "Default")
      (node (ref "X1") (pin "21") (pinfunction "S_21") (pintype "passive"))
    )
    (net (code "112") (name "unconnected-(X1P-S-Pad23)") (class "Default")
      (node (ref "X1") (pin "23") (pinfunction "S_23") (pintype "passive"))
    )
    (net (code "113") (name "unconnected-(X1R-S-Pad25)") (class "Default")
      (node (ref "X1") (pin "25") (pinfunction "S_25") (pintype "passive"))
    )
    (net (code "114") (name "unconnected-(X1T-S-Pad27)") (class "Default")
      (node (ref "X1") (pin "27") (pinfunction "S_27") (pintype "passive"))
    )
  )
)
